# daGloane.net
KiCad netlist of a schematic drawn in EAGLE
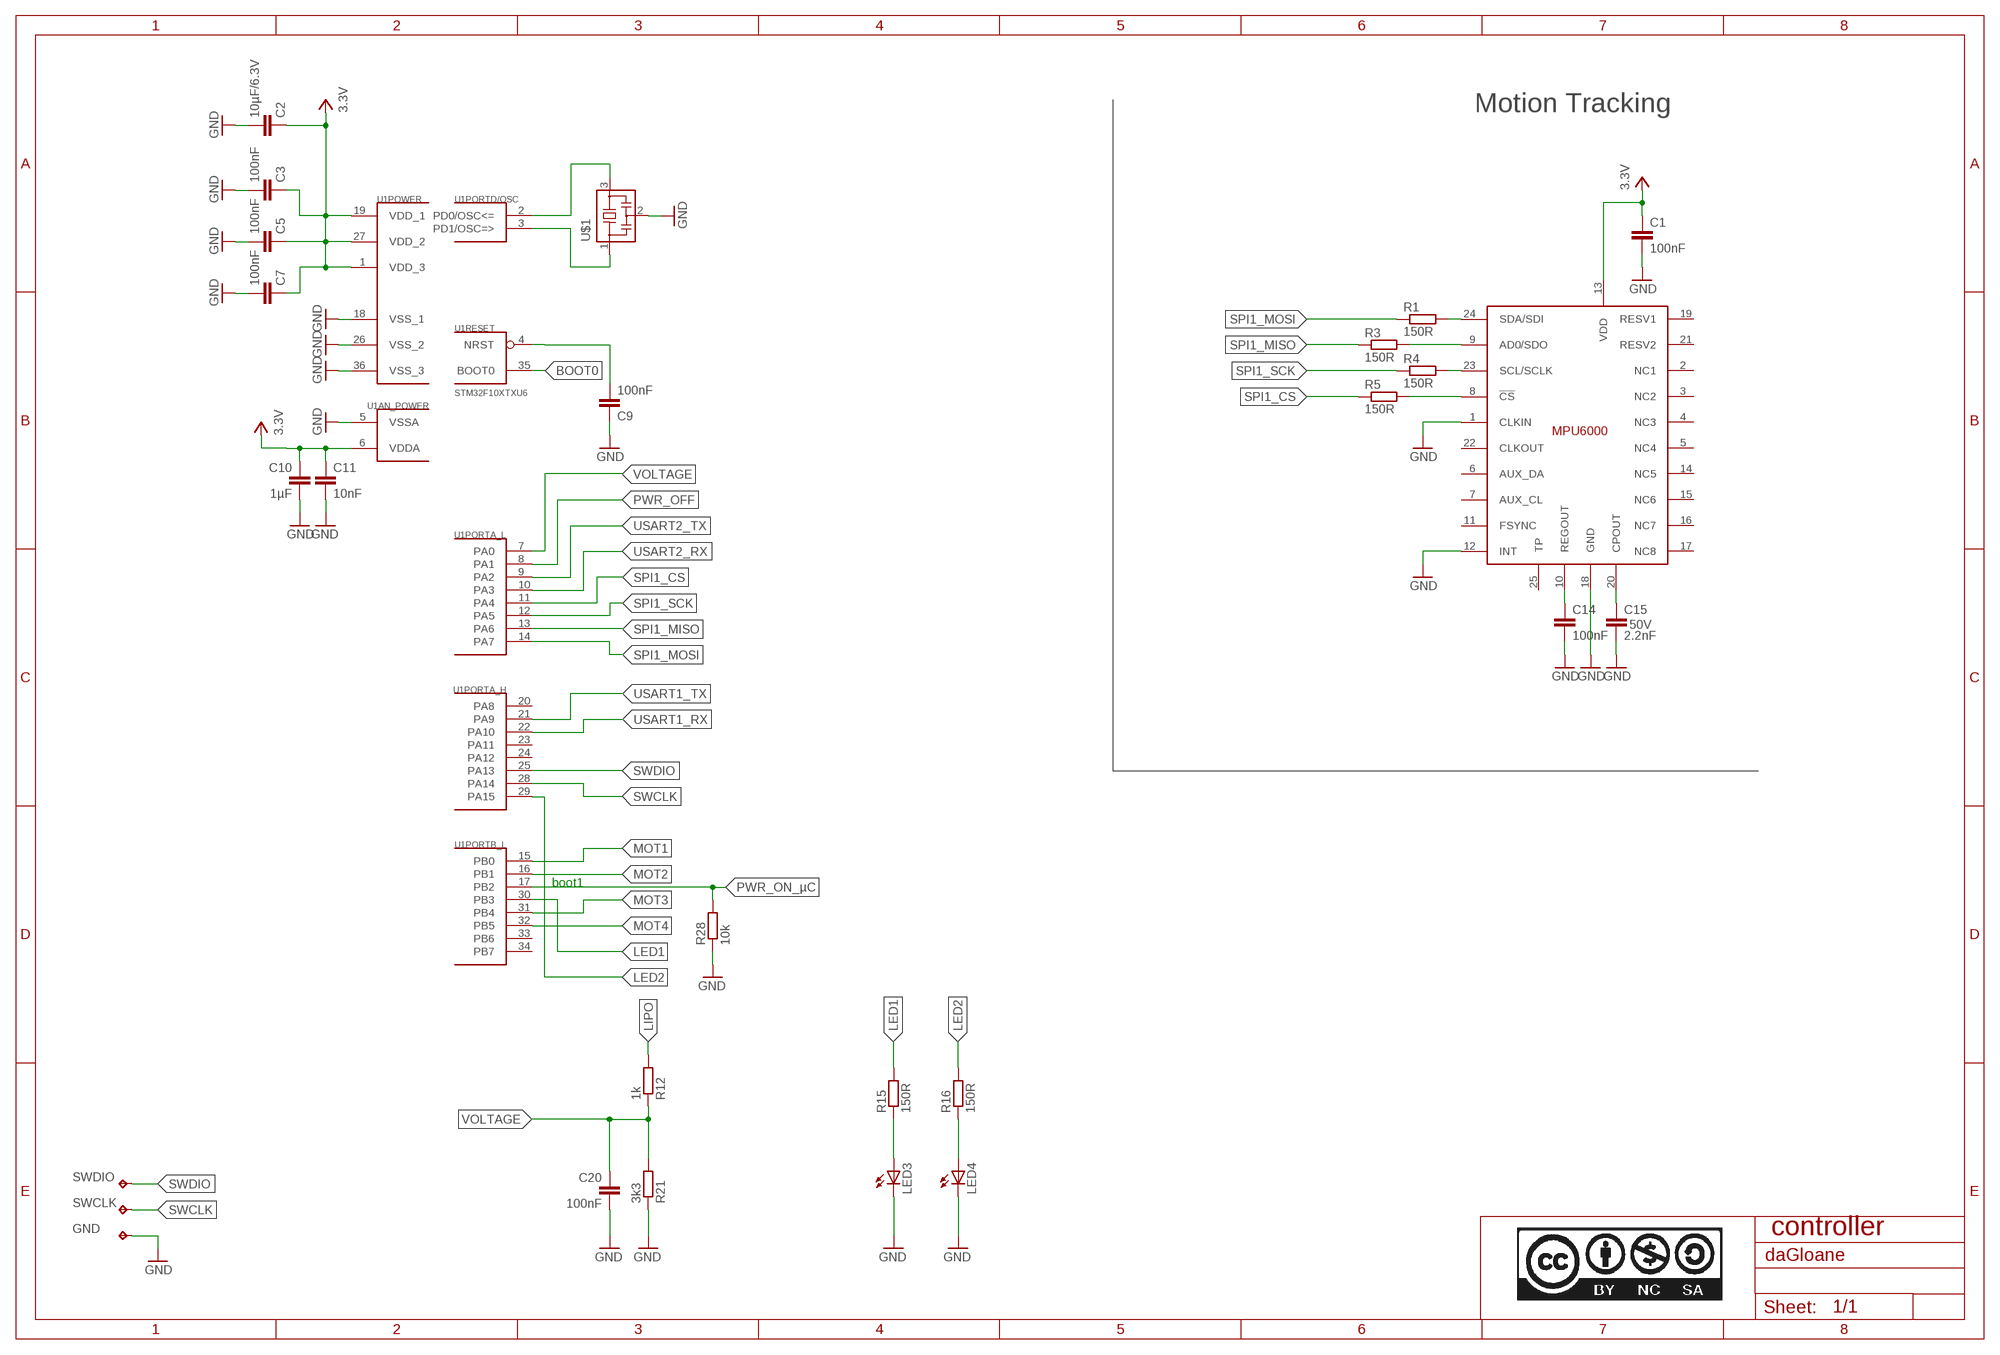
[diagram p0: schematic, sheet 1, part 1 of 3]
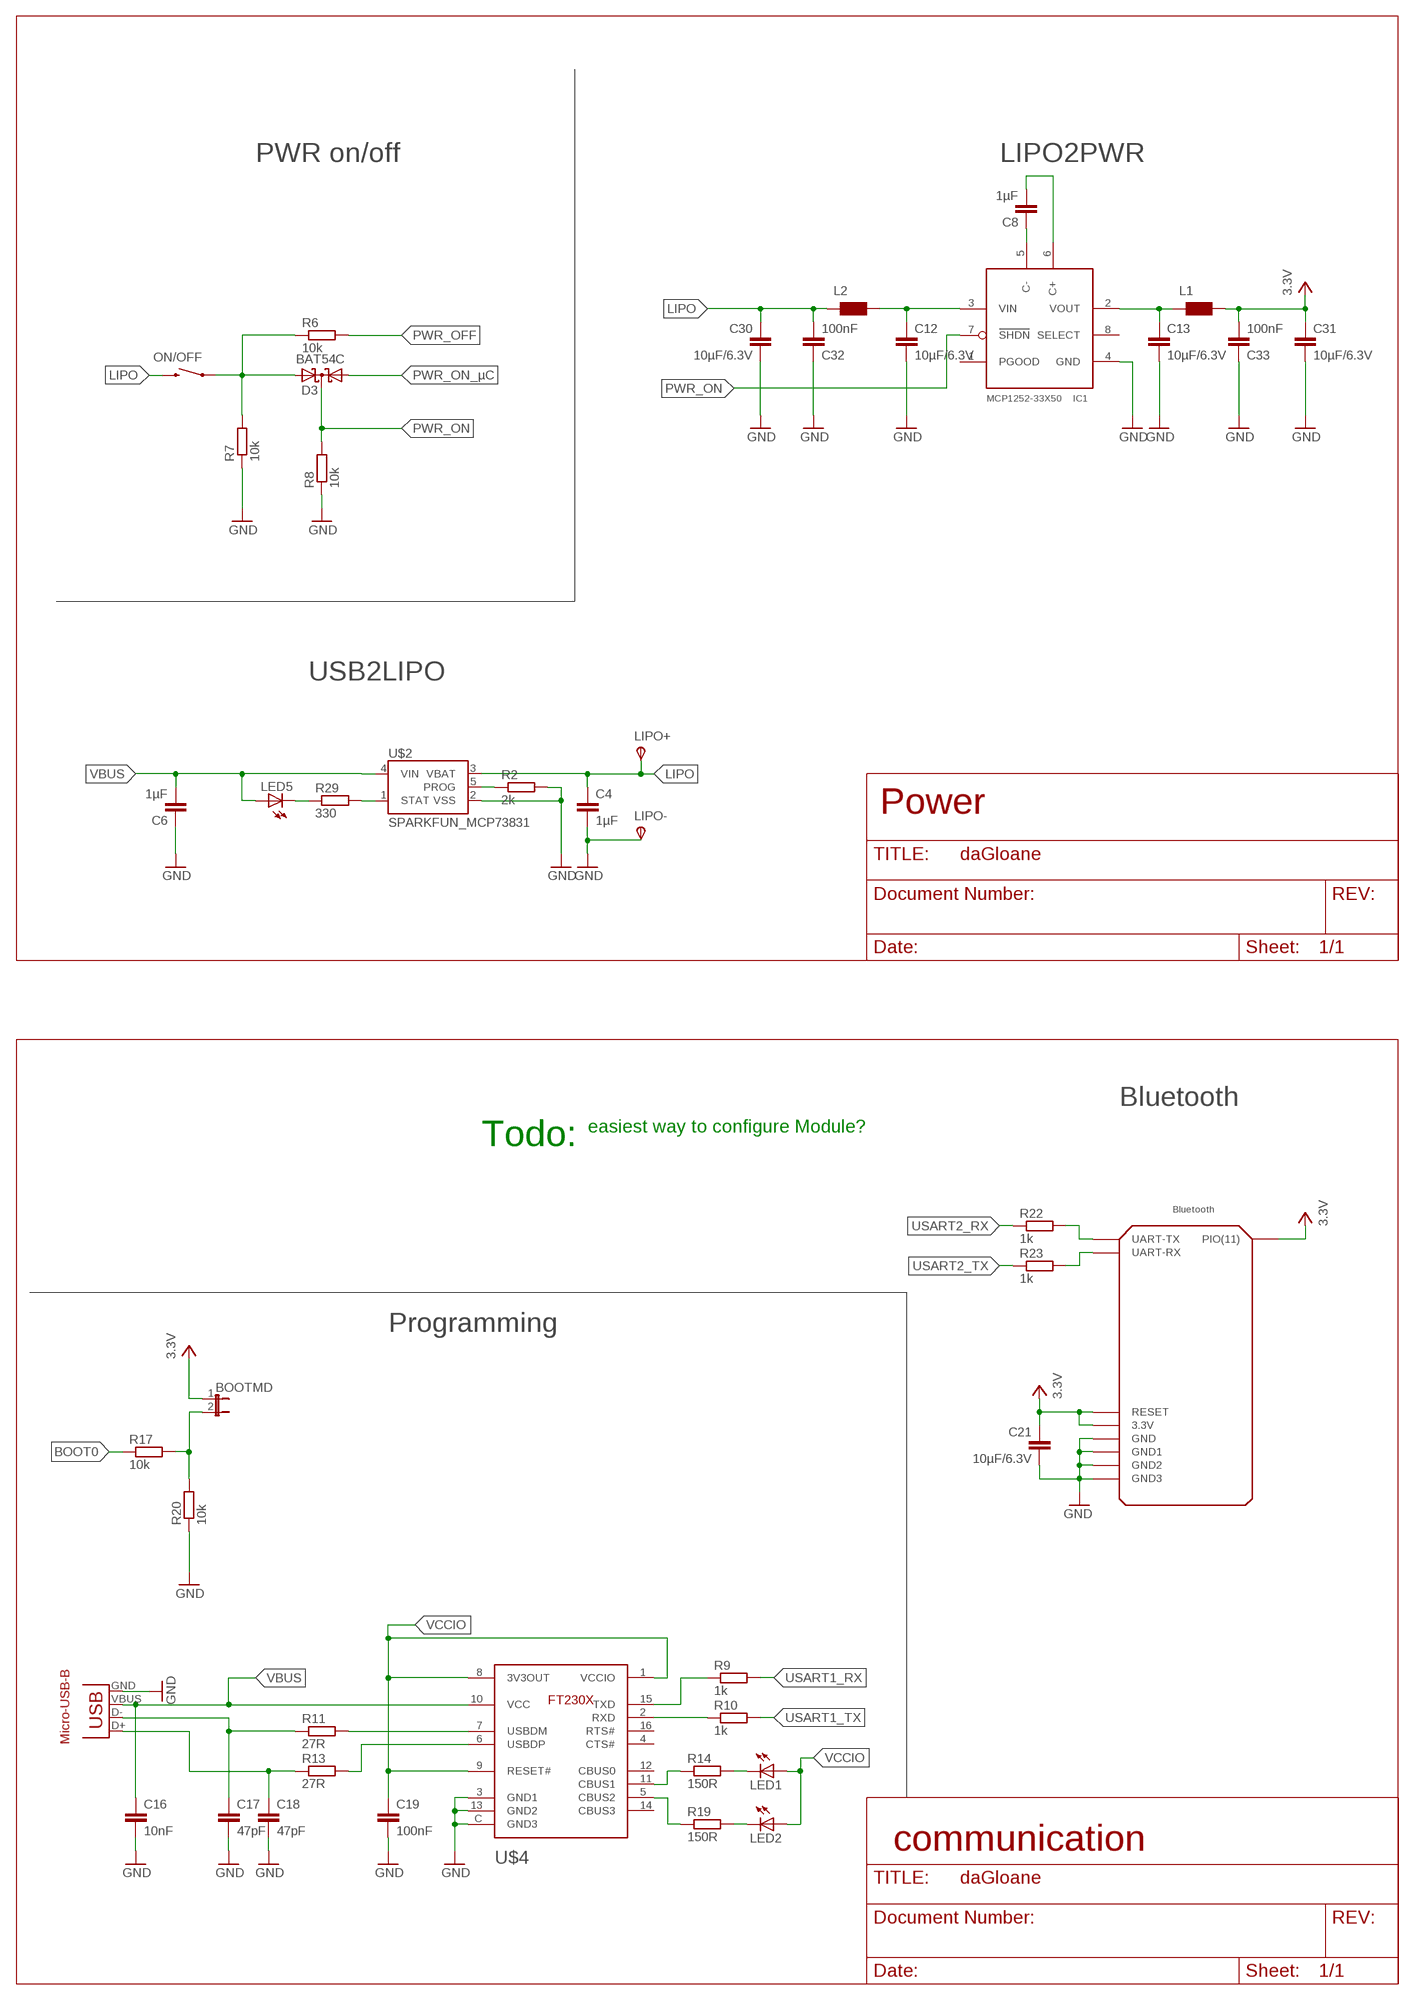
[diagram p1: schematic, sheet 1, part 2 of 3]
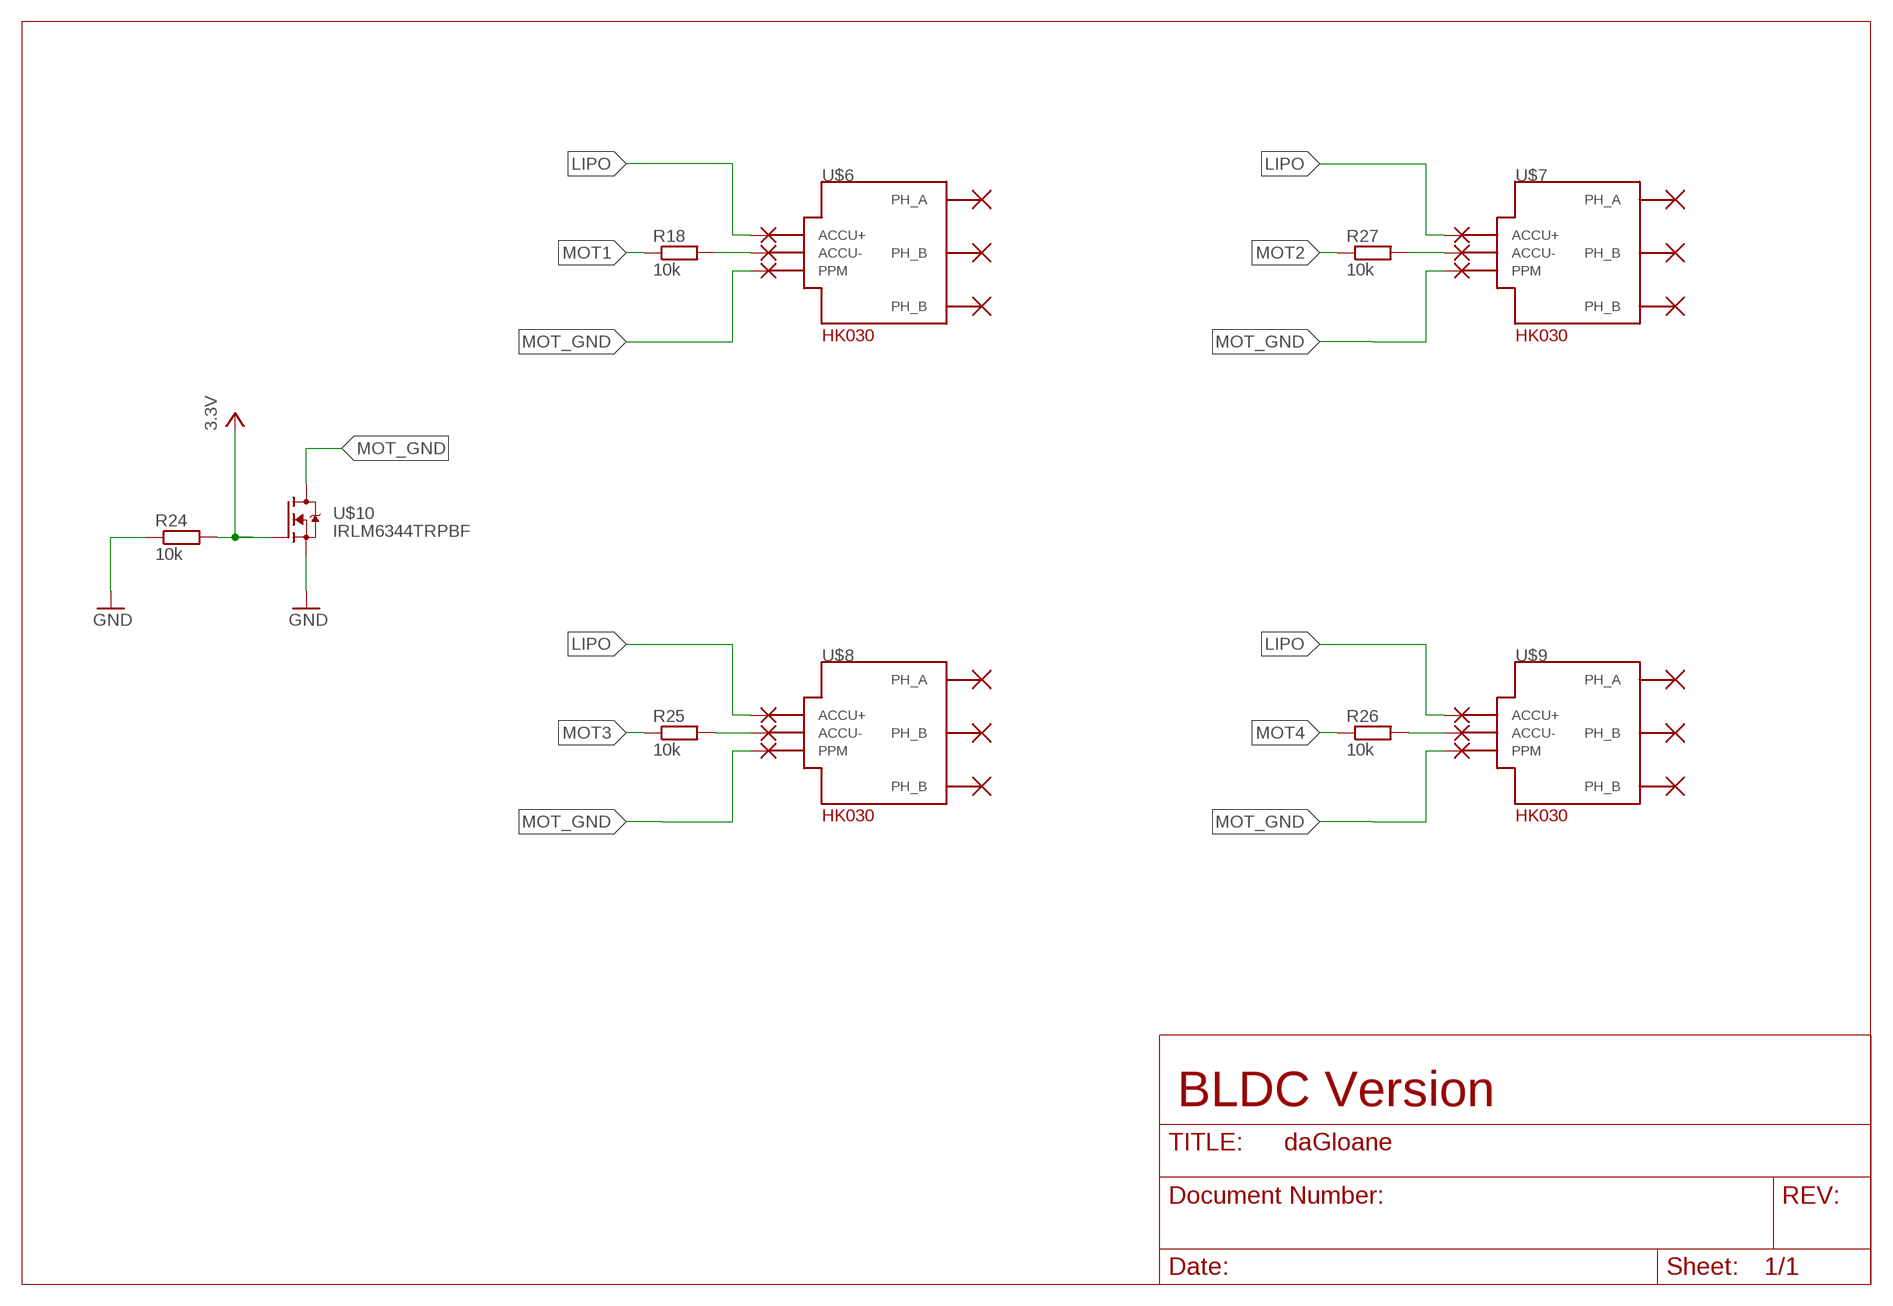
[diagram p2: schematic, sheet 1, part 3 of 3]

(export (version "E")
  (design (tool "Eeschema 10.0.6"))
  (components
    (comp (ref "BOOTMD")
      (value "JUMPER-2")
      (footprint "eagle-import:1X02_50MIL")
      (libsource (lib "eagle-import") (part "JUMPER-2"))
    )
    (comp (ref "C1")
      (value "100nF")
      (footprint "eagle-import:C0603")
      (libsource (lib "eagle-import") (part "C-EUC0603"))
    )
    (comp (ref "C2")
      (value "10µF/6.3V")
      (footprint "eagle-import:C0805")
      (libsource (lib "eagle-import") (part "C-EUC0805"))
    )
    (comp (ref "C3")
      (value "100nF")
      (footprint "eagle-import:C0603")
      (libsource (lib "eagle-import") (part "C-EUC0603"))
    )
    (comp (ref "C4")
      (value "1µF")
      (footprint "eagle-import:C0603")
      (libsource (lib "eagle-import") (part "C-EUC0603"))
    )
    (comp (ref "C5")
      (value "100nF")
      (footprint "eagle-import:C0603")
      (libsource (lib "eagle-import") (part "C-EUC0603"))
    )
    (comp (ref "C6")
      (value "1µF")
      (footprint "eagle-import:C0603")
      (libsource (lib "eagle-import") (part "C-EUC0603"))
    )
    (comp (ref "C7")
      (value "100nF")
      (footprint "eagle-import:C0603")
      (libsource (lib "eagle-import") (part "C-EUC0603"))
    )
    (comp (ref "C8")
      (value "1µF")
      (footprint "eagle-import:C0603")
      (libsource (lib "eagle-import") (part "C-EUC0603"))
    )
    (comp (ref "C9")
      (value "100nF")
      (footprint "eagle-import:C0603")
      (libsource (lib "eagle-import") (part "C-EUC0603"))
    )
    (comp (ref "C10")
      (value "1µF")
      (footprint "eagle-import:C0603")
      (libsource (lib "eagle-import") (part "C-EUC0603"))
    )
    (comp (ref "C11")
      (value "10nF")
      (footprint "eagle-import:C0603")
      (libsource (lib "eagle-import") (part "C-EUC0603"))
    )
    (comp (ref "C12")
      (value "10µF/6.3V")
      (footprint "eagle-import:C0805")
      (libsource (lib "eagle-import") (part "C-EUC0805"))
    )
    (comp (ref "C13")
      (value "10µF/6.3V")
      (footprint "eagle-import:C0805")
      (libsource (lib "eagle-import") (part "C-EUC0805"))
    )
    (comp (ref "C14")
      (value "100nF")
      (footprint "eagle-import:C0603")
      (libsource (lib "eagle-import") (part "C-EUC0603"))
    )
    (comp (ref "C15")
      (value "2.2nF")
      (footprint "eagle-import:C0603")
      (fields (field (name "VOLTAGE") "50V"))
      (libsource (lib "eagle-import") (part "C-EUC0603"))
    )
    (comp (ref "C16")
      (value "10nF")
      (footprint "eagle-import:C0603")
      (libsource (lib "eagle-import") (part "C-EUC0603"))
    )
    (comp (ref "C17")
      (value "47pF")
      (footprint "eagle-import:C0603")
      (libsource (lib "eagle-import") (part "C-EUC0603"))
    )
    (comp (ref "C18")
      (value "47pF")
      (footprint "eagle-import:C0603")
      (libsource (lib "eagle-import") (part "C-EUC0603"))
    )
    (comp (ref "C19")
      (value "100nF")
      (footprint "eagle-import:C0603")
      (libsource (lib "eagle-import") (part "C-EUC0603"))
    )
    (comp (ref "C20")
      (value "100nF")
      (footprint "eagle-import:C0603")
      (libsource (lib "eagle-import") (part "C-EUC0603"))
    )
    (comp (ref "C21")
      (value "10µF/6.3V")
      (footprint "eagle-import:C0805")
      (libsource (lib "eagle-import") (part "C-EUC0805"))
    )
    (comp (ref "C30")
      (value "10µF/6.3V")
      (footprint "eagle-import:C0805")
      (libsource (lib "eagle-import") (part "C-EUC0805"))
    )
    (comp (ref "C31")
      (value "10µF/6.3V")
      (footprint "eagle-import:C0805")
      (libsource (lib "eagle-import") (part "C-EUC0805"))
    )
    (comp (ref "C32")
      (value "100nF")
      (footprint "eagle-import:C0603")
      (libsource (lib "eagle-import") (part "C-EUC0603"))
    )
    (comp (ref "C33")
      (value "100nF")
      (footprint "eagle-import:C0603")
      (libsource (lib "eagle-import") (part "C-EUC0603"))
    )
    (comp (ref "D3")
      (value "BAT54C")
      (footprint "eagle-import:SOT23")
      (libsource (lib "eagle-import") (part "BAT54C"))
    )
    (comp (ref "GND")
      (value "TESTPAD_TPB1,27")
      (footprint "eagle-import:TESTPAD_B1,27")
      (libsource (lib "eagle-import") (part "TESTPAD_TPB1,27"))
    )
    (comp (ref "IC1")
      (value "MCP1252-33X50")
      (footprint "eagle-import:MSOP8")
      (libsource (lib "eagle-import") (part "MCP1252-33X50"))
    )
    (comp (ref "L1")
      (value "WUERTH-ELEKTRONIK_WE-KI_0805_B")
      (footprint "eagle-import:WUERTH-ELEKTRONIK_WE-KI_0805_B")
      (libsource (lib "eagle-import") (part "WUERTH-ELEKTRONIK_WE-KI_0805_B"))
    )
    (comp (ref "L2")
      (value "WUERTH-ELEKTRONIK_WE-KI_0805_B")
      (footprint "eagle-import:WUERTH-ELEKTRONIK_WE-KI_0805_B")
      (libsource (lib "eagle-import") (part "WUERTH-ELEKTRONIK_WE-KI_0805_B"))
    )
    (comp (ref "LED1")
      (value "LEDCHIPLED_0603")
      (footprint "eagle-import:CHIPLED_0603")
      (libsource (lib "eagle-import") (part "LEDCHIPLED_0603"))
    )
    (comp (ref "LED2")
      (value "LEDCHIPLED_0603")
      (footprint "eagle-import:CHIPLED_0603")
      (libsource (lib "eagle-import") (part "LEDCHIPLED_0603"))
    )
    (comp (ref "LED3")
      (value "LEDCHIPLED_0603")
      (footprint "eagle-import:CHIPLED_0603")
      (libsource (lib "eagle-import") (part "LEDCHIPLED_0603"))
    )
    (comp (ref "LED4")
      (value "LEDCHIPLED_0603")
      (footprint "eagle-import:CHIPLED_0603")
      (libsource (lib "eagle-import") (part "LEDCHIPLED_0603"))
    )
    (comp (ref "LED5")
      (value "LEDCHIPLED_0603")
      (footprint "eagle-import:CHIPLED_0603")
      (libsource (lib "eagle-import") (part "LEDCHIPLED_0603"))
    )
    (comp (ref "LIPO+")
      (value "TPSPAD1-13")
      (footprint "eagle-import:P1-13")
      (libsource (lib "eagle-import") (part "TPSPAD1-13"))
    )
    (comp (ref "LIPO-")
      (value "TPSPAD1-13")
      (footprint "eagle-import:P1-13")
      (libsource (lib "eagle-import") (part "TPSPAD1-13"))
    )
    (comp (ref "ON/OFF")
      (value "SWITCH-MOMENTARY-2SMD")
      (footprint "eagle-import:TACTILE_SWITCH_SMD")
      (libsource (lib "eagle-import") (part "SWITCH-MOMENTARY-2SMD"))
    )
    (comp (ref "PAD1")
      (value "SMD2")
      (footprint "eagle-import:SMD1,27-2,54")
      (libsource (lib "eagle-import") (part "SMD2"))
    )
    (comp (ref "PAD2")
      (value "SMD2")
      (footprint "eagle-import:SMD1,27-2,54")
      (libsource (lib "eagle-import") (part "SMD2"))
    )
    (comp (ref "PAD3")
      (value "SMD2")
      (footprint "eagle-import:SMD1,27-2,54")
      (libsource (lib "eagle-import") (part "SMD2"))
    )
    (comp (ref "PAD4")
      (value "SMD2")
      (footprint "eagle-import:SMD1,27-2,54")
      (libsource (lib "eagle-import") (part "SMD2"))
    )
    (comp (ref "PAD5")
      (value "SMD2")
      (footprint "eagle-import:SMD1,27-2,54")
      (libsource (lib "eagle-import") (part "SMD2"))
    )
    (comp (ref "PAD6")
      (value "SMD2")
      (footprint "eagle-import:SMD1,27-2,54")
      (libsource (lib "eagle-import") (part "SMD2"))
    )
    (comp (ref "PAD7")
      (value "SMD2")
      (footprint "eagle-import:SMD1,27-2,54")
      (libsource (lib "eagle-import") (part "SMD2"))
    )
    (comp (ref "PAD8")
      (value "SMD2")
      (footprint "eagle-import:SMD1,27-2,54")
      (libsource (lib "eagle-import") (part "SMD2"))
    )
    (comp (ref "PAD9")
      (value "SMD2")
      (footprint "eagle-import:SMD1,27-2,54")
      (libsource (lib "eagle-import") (part "SMD2"))
    )
    (comp (ref "PAD10")
      (value "SMD2")
      (footprint "eagle-import:SMD1,27-2,54")
      (libsource (lib "eagle-import") (part "SMD2"))
    )
    (comp (ref "PAD11")
      (value "SMD2")
      (footprint "eagle-import:SMD1,27-2,54")
      (libsource (lib "eagle-import") (part "SMD2"))
    )
    (comp (ref "PAD12")
      (value "SMD2")
      (footprint "eagle-import:SMD1,27-2,54")
      (libsource (lib "eagle-import") (part "SMD2"))
    )
    (comp (ref "R1")
      (value "150R")
      (footprint "eagle-import:R0603")
      (libsource (lib "eagle-import") (part "R-EU_R0603"))
    )
    (comp (ref "R2")
      (value "2k")
      (footprint "eagle-import:R0603")
      (libsource (lib "eagle-import") (part "R-EU_R0603"))
    )
    (comp (ref "R3")
      (value "150R")
      (footprint "eagle-import:R0603")
      (libsource (lib "eagle-import") (part "R-EU_R0603"))
    )
    (comp (ref "R4")
      (value "150R")
      (footprint "eagle-import:R0603")
      (libsource (lib "eagle-import") (part "R-EU_R0603"))
    )
    (comp (ref "R5")
      (value "150R")
      (footprint "eagle-import:R0603")
      (libsource (lib "eagle-import") (part "R-EU_R0603"))
    )
    (comp (ref "R6")
      (value "10k")
      (footprint "eagle-import:R0603")
      (libsource (lib "eagle-import") (part "R-EU_R0603"))
    )
    (comp (ref "R7")
      (value "10k")
      (footprint "eagle-import:R0603")
      (libsource (lib "eagle-import") (part "R-EU_R0603"))
    )
    (comp (ref "R8")
      (value "10k")
      (footprint "eagle-import:R0603")
      (libsource (lib "eagle-import") (part "R-EU_R0603"))
    )
    (comp (ref "R9")
      (value "1k")
      (footprint "eagle-import:R0603")
      (libsource (lib "eagle-import") (part "R-EU_R0603"))
    )
    (comp (ref "R10")
      (value "1k")
      (footprint "eagle-import:R0603")
      (libsource (lib "eagle-import") (part "R-EU_R0603"))
    )
    (comp (ref "R11")
      (value "27R")
      (footprint "eagle-import:R0603")
      (libsource (lib "eagle-import") (part "R-EU_R0603"))
    )
    (comp (ref "R12")
      (value "1k")
      (footprint "eagle-import:R0603")
      (libsource (lib "eagle-import") (part "R-EU_R0603"))
    )
    (comp (ref "R13")
      (value "27R")
      (footprint "eagle-import:R0603")
      (libsource (lib "eagle-import") (part "R-EU_R0603"))
    )
    (comp (ref "R14")
      (value "150R")
      (footprint "eagle-import:R0603")
      (libsource (lib "eagle-import") (part "R-EU_R0603"))
    )
    (comp (ref "R15")
      (value "150R")
      (footprint "eagle-import:R0603")
      (libsource (lib "eagle-import") (part "R-EU_R0603"))
    )
    (comp (ref "R16")
      (value "150R")
      (footprint "eagle-import:R0603")
      (libsource (lib "eagle-import") (part "R-EU_R0603"))
    )
    (comp (ref "R17")
      (value "10k")
      (footprint "eagle-import:R0603")
      (libsource (lib "eagle-import") (part "R-EU_R0603"))
    )
    (comp (ref "R18")
      (value "10k")
      (footprint "eagle-import:R0603")
      (libsource (lib "eagle-import") (part "R-EU_R0603"))
    )
    (comp (ref "R19")
      (value "150R")
      (footprint "eagle-import:R0603")
      (libsource (lib "eagle-import") (part "R-EU_R0603"))
    )
    (comp (ref "R20")
      (value "10k")
      (footprint "eagle-import:R0603")
      (libsource (lib "eagle-import") (part "R-EU_R0603"))
    )
    (comp (ref "R21")
      (value "3k3")
      (footprint "eagle-import:R0603")
      (libsource (lib "eagle-import") (part "R-EU_R0603"))
    )
    (comp (ref "R22")
      (value "1k")
      (footprint "eagle-import:R0603")
      (libsource (lib "eagle-import") (part "R-EU_R0603"))
    )
    (comp (ref "R23")
      (value "1k")
      (footprint "eagle-import:R0603")
      (libsource (lib "eagle-import") (part "R-EU_R0603"))
    )
    (comp (ref "R24")
      (value "10k")
      (footprint "eagle-import:R0603")
      (libsource (lib "eagle-import") (part "R-EU_R0603"))
    )
    (comp (ref "R25")
      (value "10k")
      (footprint "eagle-import:R0603")
      (libsource (lib "eagle-import") (part "R-EU_R0603"))
    )
    (comp (ref "R26")
      (value "10k")
      (footprint "eagle-import:R0603")
      (libsource (lib "eagle-import") (part "R-EU_R0603"))
    )
    (comp (ref "R27")
      (value "10k")
      (footprint "eagle-import:R0603")
      (libsource (lib "eagle-import") (part "R-EU_R0603"))
    )
    (comp (ref "R28")
      (value "10k")
      (footprint "eagle-import:R0603")
      (libsource (lib "eagle-import") (part "R-EU_R0603"))
    )
    (comp (ref "R29")
      (value "330")
      (footprint "eagle-import:R0603")
      (libsource (lib "eagle-import") (part "R-EU_R0603"))
    )
    (comp (ref "SWCLK")
      (value "TESTPAD_TPB1,27")
      (footprint "eagle-import:TESTPAD_B1,27")
      (libsource (lib "eagle-import") (part "TESTPAD_TPB1,27"))
    )
    (comp (ref "SWDIO")
      (value "TESTPAD_TPB1,27")
      (footprint "eagle-import:TESTPAD_B1,27")
      (libsource (lib "eagle-import") (part "TESTPAD_TPB1,27"))
    )
    (comp (ref "U$1")
      (value "MURATA-FILTER_CSTCE__G")
      (footprint "eagle-import:MURATA-FILTER_CSTCE__G")
      (libsource (lib "eagle-import") (part "MURATA-FILTER_CSTCE__G"))
    )
    (comp (ref "U$2")
      (value "SPARKFUN_MCP73831")
      (footprint "eagle-import:SPARKFUN_SOT23-5")
      (libsource (lib "eagle-import") (part "SPARKFUN_MCP73831"))
    )
    (comp (ref "U$3")
      (value "MPU6000")
      (footprint "eagle-import:MPU6000")
      (libsource (lib "eagle-import") (part "MPU6000"))
    )
    (comp (ref "U$4")
      (value "SERIAL_FT230XQ")
      (footprint "eagle-import:SERIAL_QFN4X4-16")
      (libsource (lib "eagle-import") (part "SERIAL_FT230XQ"))
    )
    (comp (ref "U$5")
      (value "BLUETOOTH_REDUCED")
      (footprint "eagle-import:BLUETOOTH_REDUCED")
      (libsource (lib "eagle-import") (part "BLUETOOTH_REDUCED"))
    )
    (comp (ref "U$10")
      (value "IRLM6344TRPBF")
      (footprint "eagle-import:MICRO3(SOT-23)")
      (libsource (lib "eagle-import") (part "IRLM6344TRPBF"))
    )
    (comp (ref "U1")
      (value "STM32F10XTXU6")
      (footprint "eagle-import:VFQFPN36")
      (libsource (lib "eagle-import") (part "STM32F10XTXU6"))
    )
    (comp (ref "X2")
      (value "SPARKFUN-CONNECTORS_USB-MICROB")
      (footprint "eagle-import:SPARKFUN-CONNECTORS_USB-MICROB")
      (libsource (lib "eagle-import") (part "SPARKFUN-CONNECTORS_USB-MICROB"))
    )
  )
  (nets
    (net (code "1") (name "3.3V") (class "Default")
      (node (ref "BOOTMD") (pin "1") (pinfunction "1_1") (pintype "passive"))
      (node (ref "C1") (pin "1") (pinfunction "1_1") (pintype "passive"))
      (node (ref "C10") (pin "1") (pinfunction "1_1") (pintype "passive"))
      (node (ref "C11") (pin "1") (pinfunction "1_1") (pintype "passive"))
      (node (ref "C2") (pin "1") (pinfunction "1_1") (pintype "passive"))
      (node (ref "C21") (pin "1") (pinfunction "1_1") (pintype "passive"))
      (node (ref "C3") (pin "1") (pinfunction "1_1") (pintype "passive"))
      (node (ref "C31") (pin "1") (pinfunction "1_1") (pintype "passive"))
      (node (ref "C33") (pin "2") (pinfunction "2_2") (pintype "passive"))
      (node (ref "C5") (pin "1") (pinfunction "1_1") (pintype "passive"))
      (node (ref "C7") (pin "1") (pinfunction "1_1") (pintype "passive"))
      (node (ref "L1") (pin "1") (pinfunction "2_1") (pintype "passive"))
      (node (ref "R24") (pin "2") (pinfunction "2_2") (pintype "passive"))
      (node (ref "U$10") (pin "1") (pinfunction "G_1") (pintype "passive"))
      (node (ref "U$3") (pin "13") (pinfunction "VDD_13") (pintype "power_in"))
      (node (ref "U$5") (pin "P$11") (pinfunction "RESET_P$11") (pintype "input"))
      (node (ref "U$5") (pin "P$12") (pinfunction "3.3V_P$12") (pintype "power_in"))
      (node (ref "U$5") (pin "P$34") (pinfunction "PIO(11)_P$34") (pintype "bidirectional"))
      (node (ref "U1") (pin "1") (pinfunction "VDD_3_1") (pintype "power_in"))
      (node (ref "U1") (pin "19") (pinfunction "VDD_1_19") (pintype "power_in"))
      (node (ref "U1") (pin "27") (pinfunction "VDD_2_27") (pintype "power_in"))
      (node (ref "U1") (pin "6") (pinfunction "VDDA_6") (pintype "power_in"))
    )
    (net (code "2") (name "BOOT0") (class "Default")
      (node (ref "R17") (pin "1") (pinfunction "1_1") (pintype "passive"))
      (node (ref "U1") (pin "35") (pinfunction "BOOT0_35") (pintype "input"))
    )
    (net (code "3") (name "GND") (class "Default")
      (node (ref "C1") (pin "2") (pinfunction "2_2") (pintype "passive"))
      (node (ref "C10") (pin "2") (pinfunction "2_2") (pintype "passive"))
      (node (ref "C11") (pin "2") (pinfunction "2_2") (pintype "passive"))
      (node (ref "C12") (pin "2") (pinfunction "2_2") (pintype "passive"))
      (node (ref "C13") (pin "2") (pinfunction "2_2") (pintype "passive"))
      (node (ref "C14") (pin "2") (pinfunction "2_2") (pintype "passive"))
      (node (ref "C15") (pin "2") (pinfunction "2_2") (pintype "passive"))
      (node (ref "C16") (pin "2") (pinfunction "2_2") (pintype "passive"))
      (node (ref "C17") (pin "2") (pinfunction "2_2") (pintype "passive"))
      (node (ref "C18") (pin "2") (pinfunction "2_2") (pintype "passive"))
      (node (ref "C19") (pin "2") (pinfunction "2_2") (pintype "passive"))
      (node (ref "C2") (pin "2") (pinfunction "2_2") (pintype "passive"))
      (node (ref "C20") (pin "2") (pinfunction "2_2") (pintype "passive"))
      (node (ref "C21") (pin "2") (pinfunction "2_2") (pintype "passive"))
      (node (ref "C3") (pin "2") (pinfunction "2_2") (pintype "passive"))
      (node (ref "C30") (pin "2") (pinfunction "2_2") (pintype "passive"))
      (node (ref "C31") (pin "2") (pinfunction "2_2") (pintype "passive"))
      (node (ref "C32") (pin "1") (pinfunction "1_1") (pintype "passive"))
      (node (ref "C33") (pin "1") (pinfunction "1_1") (pintype "passive"))
      (node (ref "C4") (pin "2") (pinfunction "2_2") (pintype "passive"))
      (node (ref "C5") (pin "2") (pinfunction "2_2") (pintype "passive"))
      (node (ref "C6") (pin "1") (pinfunction "1_1") (pintype "passive"))
      (node (ref "C7") (pin "2") (pinfunction "2_2") (pintype "passive"))
      (node (ref "C9") (pin "1") (pinfunction "1_1") (pintype "passive"))
      (node (ref "GND") (pin "PP") (pinfunction "TP_PP") (pintype "input"))
      (node (ref "IC1") (pin "4") (pinfunction "GND_4") (pintype "power_in"))
      (node (ref "LED3") (pin "C") (pinfunction "C_C") (pintype "passive"))
      (node (ref "LED4") (pin "C") (pinfunction "C_C") (pintype "passive"))
      (node (ref "LIPO-") (pin "TP") (pinfunction "PP_TP") (pintype "input"))
      (node (ref "R2") (pin "2") (pinfunction "2_2") (pintype "passive"))
      (node (ref "R20") (pin "1") (pinfunction "1_1") (pintype "passive"))
      (node (ref "R21") (pin "1") (pinfunction "1_1") (pintype "passive"))
      (node (ref "R24") (pin "1") (pinfunction "1_1") (pintype "passive"))
      (node (ref "R28") (pin "1") (pinfunction "1_1") (pintype "passive"))
      (node (ref "R7") (pin "1") (pinfunction "1_1") (pintype "passive"))
      (node (ref "R8") (pin "1") (pinfunction "1_1") (pintype "passive"))
      (node (ref "U$1") (pin "2") (pinfunction "2_2") (pintype "passive"))
      (node (ref "U$10") (pin "2") (pinfunction "S_2") (pintype "passive"))
      (node (ref "U$2") (pin "2") (pinfunction "VSS_2") (pintype "power_in"))
      (node (ref "U$3") (pin "1") (pinfunction "CLKIN_1") (pintype "input"))
      (node (ref "U$3") (pin "12") (pinfunction "INT_12") (pintype "output"))
      (node (ref "U$3") (pin "18") (pinfunction "GND_18") (pintype "power_in"))
      (node (ref "U$4") (pin "13") (pinfunction "GND2_13") (pintype "power_in"))
      (node (ref "U$4") (pin "3") (pinfunction "GND1_3") (pintype "power_in"))
      (node (ref "U$4") (pin "C") (pinfunction "GND3_C") (pintype "power_in"))
      (node (ref "U$5") (pin "P$13") (pinfunction "GND_P$13") (pintype "power_in"))
      (node (ref "U$5") (pin "P$14") (pinfunction "GND1_P$14") (pintype "power_in"))
      (node (ref "U$5") (pin "P$21") (pinfunction "GND2_P$21") (pintype "power_in"))
      (node (ref "U$5") (pin "P$22") (pinfunction "GND3_P$22") (pintype "power_in"))
      (node (ref "U1") (pin "18") (pinfunction "VSS_1_18") (pintype "power_in"))
      (node (ref "U1") (pin "26") (pinfunction "VSS_2_26") (pintype "power_in"))
      (node (ref "U1") (pin "36") (pinfunction "VSS_3_36") (pintype "power_in"))
      (node (ref "U1") (pin "5") (pinfunction "VSSA_5") (pintype "power_in"))
      (node (ref "X2") (pin "GND") (pinfunction "GND_GND") (pintype "bidirectional"))
    )
    (net (code "4") (name "LED1") (class "Default")
      (node (ref "R15") (pin "2") (pinfunction "2_2") (pintype "passive"))
      (node (ref "U1") (pin "30") (pinfunction "PB3_30") (pintype "bidirectional"))
    )
    (net (code "5") (name "LED2") (class "Default")
      (node (ref "R16") (pin "2") (pinfunction "2_2") (pintype "passive"))
      (node (ref "U1") (pin "29") (pinfunction "PA15_29") (pintype "bidirectional"))
    )
    (net (code "6") (name "LIPO") (class "Default")
      (node (ref "C30") (pin "1") (pinfunction "1_1") (pintype "passive"))
      (node (ref "C32") (pin "2") (pinfunction "2_2") (pintype "passive"))
      (node (ref "C4") (pin "1") (pinfunction "1_1") (pintype "passive"))
      (node (ref "L2") (pin "2") (pinfunction "1_2") (pintype "passive"))
      (node (ref "LIPO+") (pin "TP") (pinfunction "PP_TP") (pintype "input"))
      (node (ref "ON/OFF") (pin "3") (pinfunction "2_3") (pintype "passive"))
      (node (ref "PAD1") (pin "1") (pinfunction "P_1") (pintype "passive"))
      (node (ref "PAD10") (pin "1") (pinfunction "P_1") (pintype "passive"))
      (node (ref "PAD4") (pin "1") (pinfunction "P_1") (pintype "passive"))
      (node (ref "PAD7") (pin "1") (pinfunction "P_1") (pintype "passive"))
      (node (ref "R12") (pin "2") (pinfunction "2_2") (pintype "passive"))
      (node (ref "U$2") (pin "3") (pinfunction "VBAT_3") (pintype "power_in"))
    )
    (net (code "7") (name "MOT1") (class "Default")
      (node (ref "R18") (pin "1") (pinfunction "1_1") (pintype "passive"))
      (node (ref "U1") (pin "15") (pinfunction "PB0_15") (pintype "bidirectional"))
    )
    (net (code "8") (name "MOT2") (class "Default")
      (node (ref "R27") (pin "1") (pinfunction "1_1") (pintype "passive"))
      (node (ref "U1") (pin "16") (pinfunction "PB1_16") (pintype "bidirectional"))
    )
    (net (code "9") (name "MOT3") (class "Default")
      (node (ref "R25") (pin "1") (pinfunction "1_1") (pintype "passive"))
      (node (ref "U1") (pin "31") (pinfunction "PB4_31") (pintype "bidirectional"))
    )
    (net (code "10") (name "MOT4") (class "Default")
      (node (ref "R26") (pin "1") (pinfunction "1_1") (pintype "passive"))
      (node (ref "U1") (pin "32") (pinfunction "PB5_32") (pintype "bidirectional"))
    )
    (net (code "11") (name "MOT_GND") (class "Default")
      (node (ref "PAD12") (pin "1") (pinfunction "P_1") (pintype "passive"))
      (node (ref "PAD3") (pin "1") (pinfunction "P_1") (pintype "passive"))
      (node (ref "PAD6") (pin "1") (pinfunction "P_1") (pintype "passive"))
      (node (ref "PAD9") (pin "1") (pinfunction "P_1") (pintype "passive"))
      (node (ref "U$10") (pin "3") (pinfunction "D_3") (pintype "passive"))
    )
    (net (code "12") (name "Net-(BOOTMD-Pad2)") (class "Default")
      (node (ref "BOOTMD") (pin "2") (pinfunction "2_2") (pintype "passive"))
      (node (ref "R17") (pin "2") (pinfunction "2_2") (pintype "passive"))
      (node (ref "R20") (pin "2") (pinfunction "2_2") (pintype "passive"))
    )
    (net (code "13") (name "Net-(C17-Pad1)") (class "Default")
      (node (ref "C17") (pin "1") (pinfunction "1_1") (pintype "passive"))
      (node (ref "R11") (pin "1") (pinfunction "1_1") (pintype "passive"))
      (node (ref "X2") (pin "D-") (pinfunction "D-_D-") (pintype "bidirectional"))
    )
    (net (code "14") (name "Net-(C18-Pad1)") (class "Default")
      (node (ref "C18") (pin "1") (pinfunction "1_1") (pintype "passive"))
      (node (ref "R13") (pin "1") (pinfunction "1_1") (pintype "passive"))
      (node (ref "X2") (pin "D+") (pinfunction "D+_D+") (pintype "bidirectional"))
    )
    (net (code "15") (name "Net-(D3-A2)") (class "Default")
      (node (ref "D3") (pin "2") (pinfunction "A2_2") (pintype "passive"))
      (node (ref "ON/OFF") (pin "1") (pinfunction "1_1") (pintype "passive"))
      (node (ref "R6") (pin "1") (pinfunction "1_1") (pintype "passive"))
      (node (ref "R7") (pin "2") (pinfunction "2_2") (pintype "passive"))
    )
    (net (code "16") (name "Net-(IC1-C+)") (class "Default")
      (node (ref "C8") (pin "2") (pinfunction "2_2") (pintype "passive"))
      (node (ref "IC1") (pin "6") (pinfunction "C+_6") (pintype "passive"))
    )
    (net (code "17") (name "Net-(IC1-C-)") (class "Default")
      (node (ref "C8") (pin "1") (pinfunction "1_1") (pintype "passive"))
      (node (ref "IC1") (pin "5") (pinfunction "C-_5") (pintype "passive"))
    )
    (net (code "18") (name "Net-(IC1-VIN)") (class "Default")
      (node (ref "C12") (pin "1") (pinfunction "1_1") (pintype "passive"))
      (node (ref "IC1") (pin "3") (pinfunction "VIN_3") (pintype "power_in"))
      (node (ref "L2") (pin "1") (pinfunction "2_1") (pintype "passive"))
    )
    (net (code "19") (name "Net-(IC1-VOUT)") (class "Default")
      (node (ref "C13") (pin "1") (pinfunction "1_1") (pintype "passive"))
      (node (ref "IC1") (pin "2") (pinfunction "VOUT_2") (pintype "output"))
      (node (ref "L1") (pin "2") (pinfunction "1_2") (pintype "passive"))
    )
    (net (code "20") (name "Net-(LED1-PadC)") (class "Default")
      (node (ref "LED1") (pin "C") (pinfunction "C_C") (pintype "passive"))
      (node (ref "R14") (pin "2") (pinfunction "2_2") (pintype "passive"))
    )
    (net (code "21") (name "Net-(LED2-PadC)") (class "Default")
      (node (ref "LED2") (pin "C") (pinfunction "C_C") (pintype "passive"))
      (node (ref "R19") (pin "2") (pinfunction "2_2") (pintype "passive"))
    )
    (net (code "22") (name "Net-(LED3-PadA)") (class "Default")
      (node (ref "LED3") (pin "A") (pinfunction "A_A") (pintype "passive"))
      (node (ref "R15") (pin "1") (pinfunction "1_1") (pintype "passive"))
    )
    (net (code "23") (name "Net-(LED4-PadA)") (class "Default")
      (node (ref "LED4") (pin "A") (pinfunction "A_A") (pintype "passive"))
      (node (ref "R16") (pin "1") (pinfunction "1_1") (pintype "passive"))
    )
    (net (code "24") (name "Net-(LED5-PadC)") (class "Default")
      (node (ref "LED5") (pin "C") (pinfunction "C_C") (pintype "passive"))
      (node (ref "R29") (pin "1") (pinfunction "1_1") (pintype "passive"))
    )
    (net (code "25") (name "Net-(PAD2-P)") (class "Default")
      (node (ref "PAD2") (pin "1") (pinfunction "P_1") (pintype "passive"))
      (node (ref "R18") (pin "2") (pinfunction "2_2") (pintype "passive"))
    )
    (net (code "26") (name "Net-(PAD5-P)") (class "Default")
      (node (ref "PAD5") (pin "1") (pinfunction "P_1") (pintype "passive"))
      (node (ref "R25") (pin "2") (pinfunction "2_2") (pintype "passive"))
    )
    (net (code "27") (name "Net-(PAD8-P)") (class "Default")
      (node (ref "PAD8") (pin "1") (pinfunction "P_1") (pintype "passive"))
      (node (ref "R26") (pin "2") (pinfunction "2_2") (pintype "passive"))
    )
    (net (code "28") (name "Net-(PAD11-P)") (class "Default")
      (node (ref "PAD11") (pin "1") (pinfunction "P_1") (pintype "passive"))
      (node (ref "R27") (pin "2") (pinfunction "2_2") (pintype "passive"))
    )
    (net (code "29") (name "Net-(U$2-PROG)") (class "Default")
      (node (ref "R2") (pin "1") (pinfunction "1_1") (pintype "passive"))
      (node (ref "U$2") (pin "5") (pinfunction "PROG_5") (pintype "input"))
    )
    (net (code "30") (name "Net-(U$2-STAT)") (class "Default")
      (node (ref "R29") (pin "2") (pinfunction "2_2") (pintype "passive"))
      (node (ref "U$2") (pin "1") (pinfunction "STAT_1") (pintype "output"))
    )
    (net (code "31") (name "Net-(U$3-AD0{slash}SDO)") (class "Default")
      (node (ref "R3") (pin "2") (pinfunction "2_2") (pintype "passive"))
      (node (ref "U$3") (pin "9") (pinfunction "AD0/SDO_9") (pintype "output"))
    )
    (net (code "32") (name "Net-(U$3-CPOUT)") (class "Default")
      (node (ref "C15") (pin "1") (pinfunction "1_1") (pintype "passive"))
      (node (ref "U$3") (pin "20") (pinfunction "CPOUT_20") (pintype "bidirectional"))
    )
    (net (code "33") (name "Net-(U$3-REGOUT)") (class "Default")
      (node (ref "C14") (pin "1") (pinfunction "1_1") (pintype "passive"))
      (node (ref "U$3") (pin "10") (pinfunction "REGOUT_10") (pintype "bidirectional"))
    )
    (net (code "34") (name "Net-(U$3-SCL{slash}SCLK)") (class "Default")
      (node (ref "R4") (pin "2") (pinfunction "2_2") (pintype "passive"))
      (node (ref "U$3") (pin "23") (pinfunction "SCL/SCLK_23") (pintype "input"))
    )
    (net (code "35") (name "Net-(U$3-SDA{slash}SDI)") (class "Default")
      (node (ref "R1") (pin "2") (pinfunction "2_2") (pintype "passive"))
      (node (ref "U$3") (pin "24") (pinfunction "SDA/SDI_24") (pintype "input"))
    )
    (net (code "36") (name "Net-(U$3-~{CS})") (class "Default")
      (node (ref "R5") (pin "2") (pinfunction "2_2") (pintype "passive"))
      (node (ref "U$3") (pin "8") (pinfunction "~{CS}_8") (pintype "input"))
    )
    (net (code "37") (name "Net-(U$4-CBUS1)") (class "Default")
      (node (ref "R14") (pin "1") (pinfunction "1_1") (pintype "passive"))
      (node (ref "U$4") (pin "11") (pinfunction "CBUS1_11") (pintype "bidirectional"))
    )
    (net (code "38") (name "Net-(U$4-CBUS2)") (class "Default")
      (node (ref "R19") (pin "1") (pinfunction "1_1") (pintype "passive"))
      (node (ref "U$4") (pin "5") (pinfunction "CBUS2_5") (pintype "bidirectional"))
    )
    (net (code "39") (name "Net-(U$4-RXD)") (class "Default")
      (node (ref "R10") (pin "1") (pinfunction "1_1") (pintype "passive"))
      (node (ref "U$4") (pin "2") (pinfunction "RXD_2") (pintype "input"))
    )
    (net (code "40") (name "Net-(U$4-TXD)") (class "Default")
      (node (ref "R9") (pin "1") (pinfunction "1_1") (pintype "passive"))
      (node (ref "U$4") (pin "15") (pinfunction "TXD_15") (pintype "output"))
    )
    (net (code "41") (name "Net-(U$4-USBDM)") (class "Default")
      (node (ref "R11") (pin "2") (pinfunction "2_2") (pintype "passive"))
      (node (ref "U$4") (pin "7") (pinfunction "USBDM_7") (pintype "bidirectional"))
    )
    (net (code "42") (name "Net-(U$4-USBDP)") (class "Default")
      (node (ref "R13") (pin "2") (pinfunction "2_2") (pintype "passive"))
      (node (ref "U$4") (pin "6") (pinfunction "USBDP_6") (pintype "bidirectional"))
    )
    (net (code "43") (name "Net-(U$5-UART-RX)") (class "Default")
      (node (ref "R23") (pin "2") (pinfunction "2_2") (pintype "passive"))
      (node (ref "U$5") (pin "P$2") (pinfunction "UART-RX_P$2") (pintype "input"))
    )
    (net (code "44") (name "Net-(U$5-UART-TX)") (class "Default")
      (node (ref "R22") (pin "2") (pinfunction "2_2") (pintype "passive"))
      (node (ref "U$5") (pin "P$1") (pinfunction "UART-TX_P$1") (pintype "output"))
    )
    (net (code "45") (name "Net-(U1E-PD0{slash}OSC<=)") (class "Default")
      (node (ref "U$1") (pin "3") (pinfunction "3_3") (pintype "passive"))
      (node (ref "U1") (pin "2") (pinfunction "PD0/OSC<=_2") (pintype "bidirectional"))
    )
    (net (code "46") (name "Net-(U1E-PD1{slash}OSC=>)") (class "Default")
      (node (ref "U$1") (pin "1") (pinfunction "1_1") (pintype "passive"))
      (node (ref "U1") (pin "3") (pinfunction "PD1/OSC=>_3") (pintype "bidirectional"))
    )
    (net (code "47") (name "Net-(U1G-NRST)") (class "Default")
      (node (ref "C9") (pin "2") (pinfunction "2_2") (pintype "passive"))
      (node (ref "U1") (pin "4") (pinfunction "NRST_4") (pintype "input"))
    )
    (net (code "48") (name "PWR_OFF") (class "Default")
      (node (ref "R6") (pin "2") (pinfunction "2_2") (pintype "passive"))
      (node (ref "U1") (pin "8") (pinfunction "PA1_8") (pintype "bidirectional"))
    )
    (net (code "49") (name "PWR_ON") (class "Default")
      (node (ref "D3") (pin "3") (pinfunction "CC_3") (pintype "passive"))
      (node (ref "IC1") (pin "7") (pinfunction "SHDN_7") (pintype "input"))
      (node (ref "R8") (pin "2") (pinfunction "2_2") (pintype "passive"))
    )
    (net (code "50") (name "PWR_ON_µC") (class "Default")
      (node (ref "D3") (pin "1") (pinfunction "A1_1") (pintype "passive"))
      (node (ref "R28") (pin "2") (pinfunction "2_2") (pintype "passive"))
      (node (ref "U1") (pin "17") (pinfunction "PB2_17") (pintype "bidirectional"))
    )
    (net (code "51") (name "SPI1_CS") (class "Default")
      (node (ref "R5") (pin "1") (pinfunction "1_1") (pintype "passive"))
      (node (ref "U1") (pin "11") (pinfunction "PA4_11") (pintype "bidirectional"))
    )
    (net (code "52") (name "SPI1_MISO") (class "Default")
      (node (ref "R3") (pin "1") (pinfunction "1_1") (pintype "passive"))
      (node (ref "U1") (pin "13") (pinfunction "PA6_13") (pintype "bidirectional"))
    )
    (net (code "53") (name "SPI1_MOSI") (class "Default")
      (node (ref "R1") (pin "1") (pinfunction "1_1") (pintype "passive"))
      (node (ref "U1") (pin "14") (pinfunction "PA7_14") (pintype "bidirectional"))
    )
    (net (code "54") (name "SPI1_SCK") (class "Default")
      (node (ref "R4") (pin "1") (pinfunction "1_1") (pintype "passive"))
      (node (ref "U1") (pin "12") (pinfunction "PA5_12") (pintype "bidirectional"))
    )
    (net (code "55") (name "SWCLK") (class "Default")
      (node (ref "SWCLK") (pin "PP") (pinfunction "TP_PP") (pintype "input"))
      (node (ref "U1") (pin "28") (pinfunction "PA14_28") (pintype "bidirectional"))
    )
    (net (code "56") (name "SWDIO") (class "Default")
      (node (ref "SWDIO") (pin "PP") (pinfunction "TP_PP") (pintype "input"))
      (node (ref "U1") (pin "25") (pinfunction "PA13_25") (pintype "bidirectional"))
    )
    (net (code "57") (name "USART1_RX") (class "Default")
      (node (ref "R9") (pin "2") (pinfunction "2_2") (pintype "passive"))
      (node (ref "U1") (pin "22") (pinfunction "PA10_22") (pintype "bidirectional"))
    )
    (net (code "58") (name "USART1_TX") (class "Default")
      (node (ref "R10") (pin "2") (pinfunction "2_2") (pintype "passive"))
      (node (ref "U1") (pin "21") (pinfunction "PA9_21") (pintype "bidirectional"))
    )
    (net (code "59") (name "USART2_RX") (class "Default")
      (node (ref "R22") (pin "1") (pinfunction "1_1") (pintype "passive"))
      (node (ref "U1") (pin "10") (pinfunction "PA3_10") (pintype "bidirectional"))
    )
    (net (code "60") (name "USART2_TX") (class "Default")
      (node (ref "R23") (pin "1") (pinfunction "1_1") (pintype "passive"))
      (node (ref "U1") (pin "9") (pinfunction "PA2_9") (pintype "bidirectional"))
    )
    (net (code "61") (name "VBUS") (class "Default")
      (node (ref "C16") (pin "1") (pinfunction "1_1") (pintype "passive"))
      (node (ref "C6") (pin "2") (pinfunction "2_2") (pintype "passive"))
      (node (ref "LED5") (pin "A") (pinfunction "A_A") (pintype "passive"))
      (node (ref "U$2") (pin "4") (pinfunction "VIN_4") (pintype "power_in"))
      (node (ref "U$4") (pin "10") (pinfunction "VCC_10") (pintype "power_in"))
      (node (ref "X2") (pin "VBUS") (pinfunction "VBUS_VBUS") (pintype "bidirectional"))
    )
    (net (code "62") (name "VCCIO") (class "Default")
      (node (ref "C19") (pin "1") (pinfunction "1_1") (pintype "passive"))
      (node (ref "LED1") (pin "A") (pinfunction "A_A") (pintype "passive"))
      (node (ref "LED2") (pin "A") (pinfunction "A_A") (pintype "passive"))
      (node (ref "U$4") (pin "1") (pinfunction "VCCIO_1") (pintype "input"))
      (node (ref "U$4") (pin "8") (pinfunction "3V3OUT_8") (pintype "output"))
      (node (ref "U$4") (pin "9") (pinfunction "RESET#_9") (pintype "input"))
    )
    (net (code "63") (name "VOLTAGE") (class "Default")
      (node (ref "C20") (pin "1") (pinfunction "1_1") (pintype "passive"))
      (node (ref "R12") (pin "1") (pinfunction "1_1") (pintype "passive"))
      (node (ref "R21") (pin "2") (pinfunction "2_2") (pintype "passive"))
      (node (ref "U1") (pin "7") (pinfunction "PA0_7") (pintype "bidirectional"))
    )
    (net (code "64") (name "unconnected-(IC1-PGOOD-Pad1)") (class "Default")
      (node (ref "IC1") (pin "1") (pinfunction "PGOOD_1") (pintype "output"))
    )
    (net (code "65") (name "unconnected-(IC1-SELECT-Pad8)") (class "Default")
      (node (ref "IC1") (pin "8") (pinfunction "SELECT_8") (pintype "input"))
    )
    (net (code "66") (name "unconnected-(U$3-AUX_CL-Pad7)") (class "Default")
      (node (ref "U$3") (pin "7") (pinfunction "AUX_CL_7") (pintype "output"))
    )
    (net (code "67") (name "unconnected-(U$3-AUX_DA-Pad6)") (class "Default")
      (node (ref "U$3") (pin "6") (pinfunction "AUX_DA_6") (pintype "bidirectional"))
    )
    (net (code "68") (name "unconnected-(U$3-CLKOUT-Pad22)") (class "Default")
      (node (ref "U$3") (pin "22") (pinfunction "CLKOUT_22") (pintype "output"))
    )
    (net (code "69") (name "unconnected-(U$3-FSYNC-Pad11)") (class "Default")
      (node (ref "U$3") (pin "11") (pinfunction "FSYNC_11") (pintype "input"))
    )
    (net (code "70") (name "unconnected-(U$3-NC1-Pad2)") (class "Default")
      (node (ref "U$3") (pin "2") (pinfunction "NC1_2") (pintype "no_connect"))
    )
    (net (code "71") (name "unconnected-(U$3-NC2-Pad3)") (class "Default")
      (node (ref "U$3") (pin "3") (pinfunction "NC2_3") (pintype "no_connect"))
    )
    (net (code "72") (name "unconnected-(U$3-NC3-Pad4)") (class "Default")
      (node (ref "U$3") (pin "4") (pinfunction "NC3_4") (pintype "no_connect"))
    )
    (net (code "73") (name "unconnected-(U$3-NC4-Pad5)") (class "Default")
      (node (ref "U$3") (pin "5") (pinfunction "NC4_5") (pintype "no_connect"))
    )
    (net (code "74") (name "unconnected-(U$3-NC5-Pad14)") (class "Default")
      (node (ref "U$3") (pin "14") (pinfunction "NC5_14") (pintype "no_connect"))
    )
    (net (code "75") (name "unconnected-(U$3-NC6-Pad15)") (class "Default")
      (node (ref "U$3") (pin "15") (pinfunction "NC6_15") (pintype "no_connect"))
    )
    (net (code "76") (name "unconnected-(U$3-NC7-Pad16)") (class "Default")
      (node (ref "U$3") (pin "16") (pinfunction "NC7_16") (pintype "no_connect"))
    )
    (net (code "77") (name "unconnected-(U$3-NC8-Pad17)") (class "Default")
      (node (ref "U$3") (pin "17") (pinfunction "NC8_17") (pintype "no_connect"))
    )
    (net (code "78") (name "unconnected-(U$3-RESV1-Pad19)") (class "Default")
      (node (ref "U$3") (pin "19") (pinfunction "RESV1_19") (pintype "no_connect"))
    )
    (net (code "79") (name "unconnected-(U$3-RESV2-Pad21)") (class "Default")
      (node (ref "U$3") (pin "21") (pinfunction "RESV2_21") (pintype "no_connect"))
    )
    (net (code "80") (name "unconnected-(U$3-TP-Pad25)") (class "Default")
      (node (ref "U$3") (pin "25") (pinfunction "TP_25") (pintype "bidirectional"))
    )
    (net (code "81") (name "unconnected-(U$4-CBUS0-Pad12)") (class "Default")
      (node (ref "U$4") (pin "12") (pinfunction "CBUS0_12") (pintype "bidirectional"))
    )
    (net (code "82") (name "unconnected-(U$4-CBUS3-Pad14)") (class "Default")
      (node (ref "U$4") (pin "14") (pinfunction "CBUS3_14") (pintype "bidirectional"))
    )
    (net (code "83") (name "unconnected-(U$4-CTS#-Pad4)") (class "Default")
      (node (ref "U$4") (pin "4") (pinfunction "CTS#_4") (pintype "bidirectional"))
    )
    (net (code "84") (name "unconnected-(U$4-RTS#-Pad16)") (class "Default")
      (node (ref "U$4") (pin "16") (pinfunction "RTS#_16") (pintype "bidirectional"))
    )
    (net (code "85") (name "unconnected-(U1B-PA8-Pad20)") (class "Default")
      (node (ref "U1") (pin "20") (pinfunction "PA8_20") (pintype "bidirectional"))
    )
    (net (code "86") (name "unconnected-(U1B-PA11-Pad23)") (class "Default")
      (node (ref "U1") (pin "23") (pinfunction "PA11_23") (pintype "bidirectional"))
    )
    (net (code "87") (name "unconnected-(U1B-PA12-Pad24)") (class "Default")
      (node (ref "U1") (pin "24") (pinfunction "PA12_24") (pintype "bidirectional"))
    )
    (net (code "88") (name "unconnected-(U1D-PB6-Pad33)") (class "Default")
      (node (ref "U1") (pin "33") (pinfunction "PB6_33") (pintype "bidirectional"))
    )
    (net (code "89") (name "unconnected-(U1D-PB7-Pad34)") (class "Default")
      (node (ref "U1") (pin "34") (pinfunction "PB7_34") (pintype "bidirectional"))
    )
  )
)
